# BMW_final.net
KiCad netlist of a schematic drawn in EAGLE
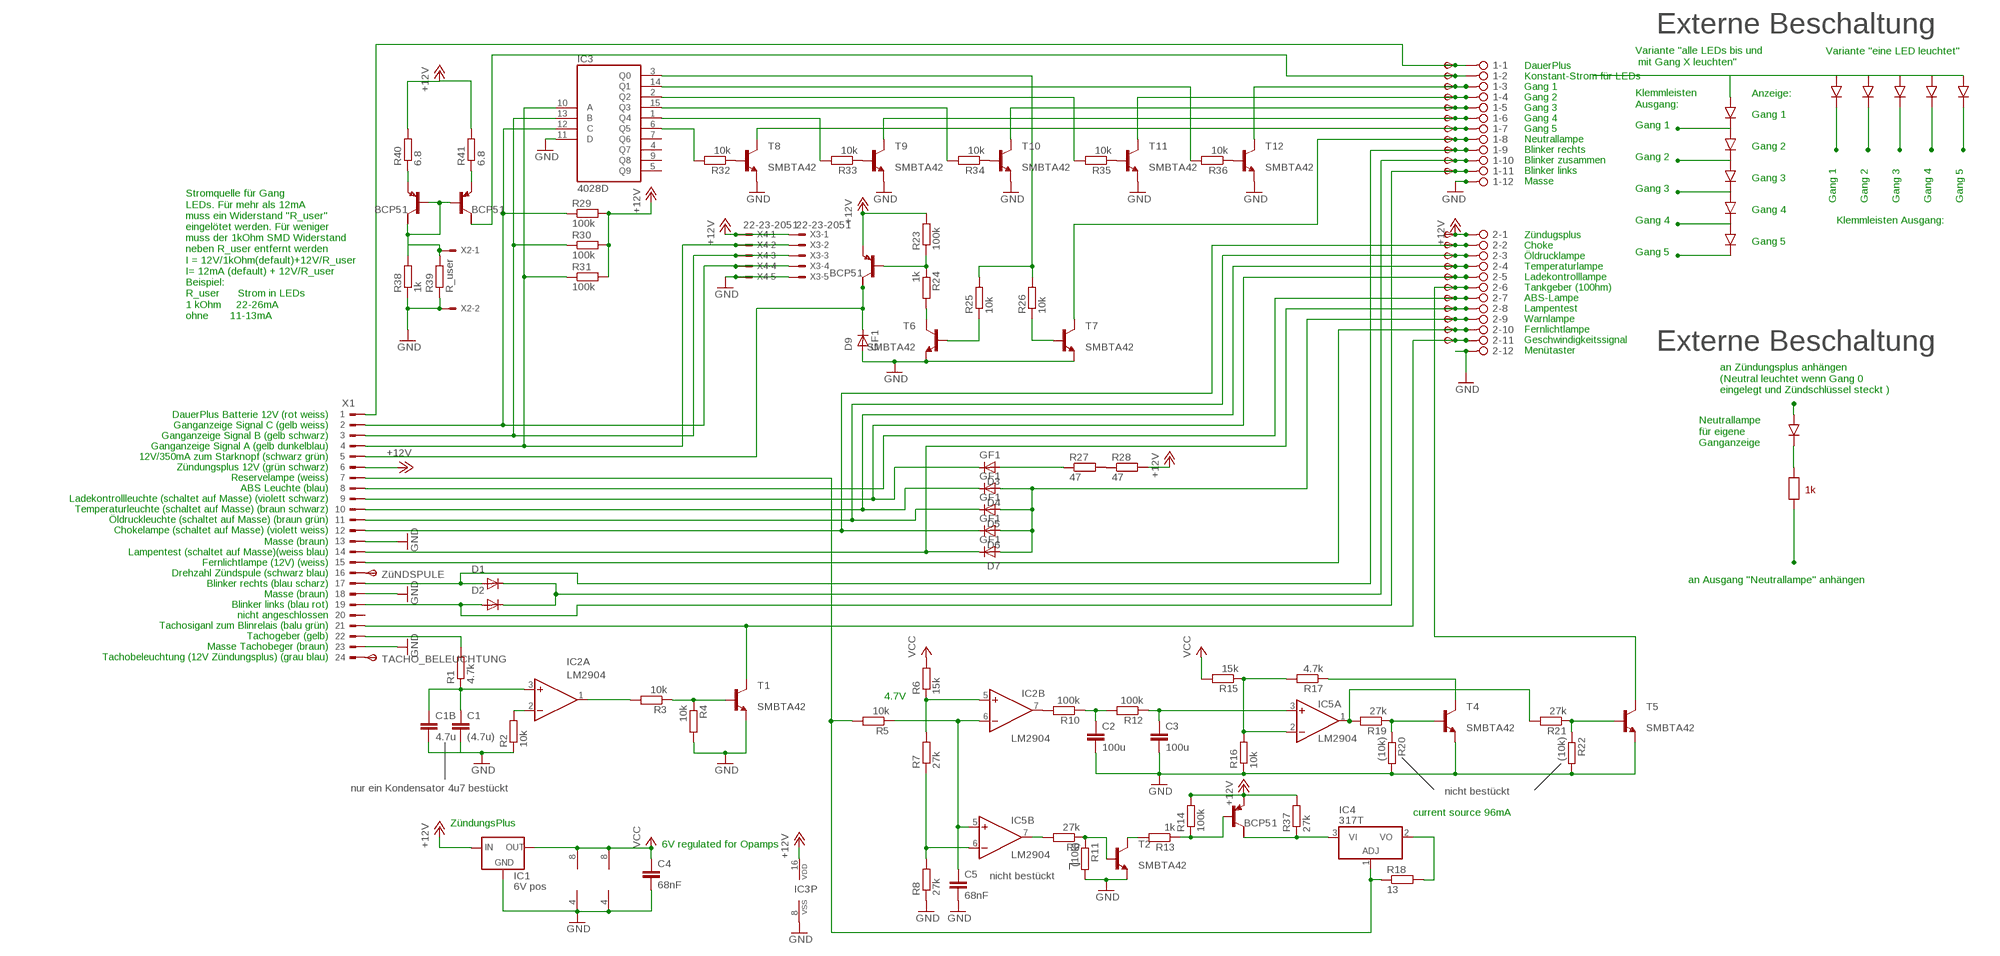
[diagram p0: schematic, sheet 1]

(export (version "E")
  (design (tool "Eeschema 10.0.6"))
  (components
    (comp (ref "1")
      (value "2081-1132")
      (footprint "eagle-import:12-PIN")
      (libsource (lib "eagle-import") (part "2081-1132"))
    )
    (comp (ref "2")
      (value "2081-1132")
      (footprint "eagle-import:12-PIN")
      (libsource (lib "eagle-import") (part "2081-1132"))
    )
    (comp (ref "C1")
      (value "(4.7u)")
      (footprint "eagle-import:C1206")
      (libsource (lib "eagle-import") (part "C-EUC1206"))
    )
    (comp (ref "C1B")
      (value "4.7u")
      (footprint "eagle-import:C0805K")
      (libsource (lib "eagle-import") (part "C-EUC0805K"))
    )
    (comp (ref "C2")
      (value "100u")
      (footprint "eagle-import:C1206K")
      (libsource (lib "eagle-import") (part "C-EUC1206K"))
    )
    (comp (ref "C3")
      (value "100u")
      (footprint "eagle-import:C1206K")
      (libsource (lib "eagle-import") (part "C-EUC1206K"))
    )
    (comp (ref "C4")
      (value "68nF")
      (footprint "eagle-import:C1206K")
      (libsource (lib "eagle-import") (part "C-EUC1206K"))
    )
    (comp (ref "C5")
      (value "68nF")
      (footprint "eagle-import:C1206K")
      (libsource (lib "eagle-import") (part "C-EUC1206K"))
    )
    (comp (ref "D1")
      (value "GF1")
      (footprint "eagle-import:SMA-DO214AC")
      (libsource (lib "eagle-import") (part "GF1"))
    )
    (comp (ref "D2")
      (value "GF1")
      (footprint "eagle-import:SMA-DO214AC")
      (libsource (lib "eagle-import") (part "GF1"))
    )
    (comp (ref "D3")
      (value "GF1")
      (footprint "eagle-import:SMA-DO214AC")
      (libsource (lib "eagle-import") (part "GF1"))
    )
    (comp (ref "D4")
      (value "GF1")
      (footprint "eagle-import:SMA-DO214AC")
      (libsource (lib "eagle-import") (part "GF1"))
    )
    (comp (ref "D5")
      (value "GF1")
      (footprint "eagle-import:SMA-DO214AC")
      (libsource (lib "eagle-import") (part "GF1"))
    )
    (comp (ref "D6")
      (value "GF1")
      (footprint "eagle-import:SMA-DO214AC")
      (libsource (lib "eagle-import") (part "GF1"))
    )
    (comp (ref "D7")
      (value "GF1")
      (footprint "eagle-import:SMA-DO214AC")
      (libsource (lib "eagle-import") (part "GF1"))
    )
    (comp (ref "D9")
      (value "GF1")
      (footprint "eagle-import:SMA-DO214AC")
      (libsource (lib "eagle-import") (part "GF1"))
    )
    (comp (ref "IC1")
      (value "6V pos")
      (footprint "eagle-import:78LXX")
      (libsource (lib "eagle-import") (part "78LXX"))
    )
    (comp (ref "IC2")
      (value "LM2904")
      (footprint "eagle-import:SO08")
      (fields (field (name "IC") "LM2904"))
      (libsource (lib "eagle-import") (part "LM358D"))
    )
    (comp (ref "IC3")
      (value "4028D")
      (footprint "eagle-import:SO16")
      (libsource (lib "eagle-import") (part "4028D"))
    )
    (comp (ref "IC4")
      (value "317T")
      (footprint "eagle-import:TO220H")
      (libsource (lib "eagle-import") (part "317T"))
    )
    (comp (ref "IC5")
      (value "LM2904")
      (footprint "eagle-import:SO08")
      (libsource (lib "eagle-import") (part "linear_BMW_LM358D"))
    )
    (comp (ref "R1")
      (value "4.7k")
      (footprint "eagle-import:R0805")
      (libsource (lib "eagle-import") (part "R-EU_R0805"))
    )
    (comp (ref "R2")
      (value "10k")
      (footprint "eagle-import:R0805")
      (libsource (lib "eagle-import") (part "R-EU_R0805"))
    )
    (comp (ref "R3")
      (value "10k")
      (footprint "eagle-import:R0805")
      (libsource (lib "eagle-import") (part "R-EU_R0805"))
    )
    (comp (ref "R4")
      (value "10k")
      (footprint "eagle-import:R0805")
      (libsource (lib "eagle-import") (part "R-EU_R0805"))
    )
    (comp (ref "R5")
      (value "10k")
      (footprint "eagle-import:R0805")
      (libsource (lib "eagle-import") (part "R-EU_R0805"))
    )
    (comp (ref "R6")
      (value "15k")
      (footprint "eagle-import:R0805")
      (libsource (lib "eagle-import") (part "R-EU_R0805"))
    )
    (comp (ref "R7")
      (value "27k")
      (footprint "eagle-import:R0805")
      (libsource (lib "eagle-import") (part "R-EU_R0805"))
    )
    (comp (ref "R8")
      (value "27k")
      (footprint "eagle-import:R0805")
      (libsource (lib "eagle-import") (part "R-EU_R0805"))
    )
    (comp (ref "R9")
      (value "27k")
      (footprint "eagle-import:R0805")
      (libsource (lib "eagle-import") (part "R-EU_R0805"))
    )
    (comp (ref "R10")
      (value "100k")
      (footprint "eagle-import:R0805")
      (libsource (lib "eagle-import") (part "R-EU_R0805"))
    )
    (comp (ref "R11")
      (value "(10k)")
      (footprint "eagle-import:R0805")
      (libsource (lib "eagle-import") (part "R-EU_R0805"))
    )
    (comp (ref "R12")
      (value "100k")
      (footprint "eagle-import:R0805")
      (libsource (lib "eagle-import") (part "R-EU_R0805"))
    )
    (comp (ref "R13")
      (value "1k")
      (footprint "eagle-import:R0805")
      (libsource (lib "eagle-import") (part "R-EU_R0805"))
    )
    (comp (ref "R14")
      (value "100k")
      (footprint "eagle-import:R0805")
      (libsource (lib "eagle-import") (part "R-EU_R0805"))
    )
    (comp (ref "R15")
      (value "15k")
      (footprint "eagle-import:R0805")
      (libsource (lib "eagle-import") (part "R-EU_R0805"))
    )
    (comp (ref "R16")
      (value "10k")
      (footprint "eagle-import:R0805")
      (libsource (lib "eagle-import") (part "R-EU_R0805"))
    )
    (comp (ref "R17")
      (value "4.7k")
      (footprint "eagle-import:R0805")
      (libsource (lib "eagle-import") (part "R-EU_R0805"))
    )
    (comp (ref "R18")
      (value "13")
      (footprint "eagle-import:0207_10")
      (libsource (lib "eagle-import") (part "R-EU_0207/10"))
    )
    (comp (ref "R19")
      (value "27k")
      (footprint "eagle-import:R0805")
      (libsource (lib "eagle-import") (part "R-EU_R0805"))
    )
    (comp (ref "R20")
      (value "(10k)")
      (footprint "eagle-import:R0805")
      (libsource (lib "eagle-import") (part "R-EU_R0805"))
    )
    (comp (ref "R21")
      (value "27k")
      (footprint "eagle-import:R0805")
      (libsource (lib "eagle-import") (part "R-EU_R0805"))
    )
    (comp (ref "R22")
      (value "(10k)")
      (footprint "eagle-import:R0805")
      (libsource (lib "eagle-import") (part "R-EU_R0805"))
    )
    (comp (ref "R23")
      (value "100k")
      (footprint "eagle-import:R0805")
      (libsource (lib "eagle-import") (part "R-EU_R0805"))
    )
    (comp (ref "R24")
      (value "1k")
      (footprint "eagle-import:R0805")
      (libsource (lib "eagle-import") (part "R-EU_R0805"))
    )
    (comp (ref "R25")
      (value "10k")
      (footprint "eagle-import:R0805")
      (libsource (lib "eagle-import") (part "R-EU_R0805"))
    )
    (comp (ref "R26")
      (value "10k")
      (footprint "eagle-import:R0805")
      (libsource (lib "eagle-import") (part "R-EU_R0805"))
    )
    (comp (ref "R27")
      (value "47")
      (footprint "eagle-import:V235_17")
      (libsource (lib "eagle-import") (part "R-EU_V235/17"))
    )
    (comp (ref "R28")
      (value "47")
      (footprint "eagle-import:V235_17")
      (libsource (lib "eagle-import") (part "R-EU_V235/17"))
    )
    (comp (ref "R29")
      (value "100k")
      (footprint "eagle-import:R0805")
      (libsource (lib "eagle-import") (part "R-EU_R0805"))
    )
    (comp (ref "R30")
      (value "100k")
      (footprint "eagle-import:R0805")
      (libsource (lib "eagle-import") (part "R-EU_R0805"))
    )
    (comp (ref "R31")
      (value "100k")
      (footprint "eagle-import:R0805")
      (libsource (lib "eagle-import") (part "R-EU_R0805"))
    )
    (comp (ref "R32")
      (value "10k")
      (footprint "eagle-import:R0805")
      (libsource (lib "eagle-import") (part "R-EU_R0805"))
    )
    (comp (ref "R33")
      (value "10k")
      (footprint "eagle-import:R0805")
      (libsource (lib "eagle-import") (part "R-EU_R0805"))
    )
    (comp (ref "R34")
      (value "10k")
      (footprint "eagle-import:R0805")
      (libsource (lib "eagle-import") (part "R-EU_R0805"))
    )
    (comp (ref "R35")
      (value "10k")
      (footprint "eagle-import:R0805")
      (libsource (lib "eagle-import") (part "R-EU_R0805"))
    )
    (comp (ref "R36")
      (value "10k")
      (footprint "eagle-import:R0805")
      (libsource (lib "eagle-import") (part "R-EU_R0805"))
    )
    (comp (ref "R37")
      (value "27k")
      (footprint "eagle-import:R0805")
      (libsource (lib "eagle-import") (part "R-EU_R0805"))
    )
    (comp (ref "R38")
      (value "1k")
      (footprint "eagle-import:R0805")
      (libsource (lib "eagle-import") (part "R-EU_R0805"))
    )
    (comp (ref "R39")
      (value "R_user")
      (footprint "eagle-import:R0805")
      (libsource (lib "eagle-import") (part "R-EU_R0805"))
    )
    (comp (ref "R40")
      (value "6.8")
      (footprint "eagle-import:R0805")
      (libsource (lib "eagle-import") (part "R-EU_R0805"))
    )
    (comp (ref "R41")
      (value "6.8")
      (footprint "eagle-import:R0805")
      (libsource (lib "eagle-import") (part "R-EU_R0805"))
    )
    (comp (ref "T")
      (value "BCP53T1")
      (footprint "eagle-import:SOT223")
      (fields (field (name "T") "BCP51"))
      (libsource (lib "eagle-import") (part "BCP53T1"))
    )
    (comp (ref "T1")
      (value "MMBTA42LT1-NPN-SOT23-BEC")
      (footprint "eagle-import:SOT23-BEC")
      (fields (field (name "T") "SMBTA42"))
      (libsource (lib "eagle-import") (part "-NPN-SOT23-BECMMBTA42LT1"))
    )
    (comp (ref "T2")
      (value "MMBTA42LT1-NPN-SOT23-BEC")
      (footprint "eagle-import:SOT23-BEC")
      (fields (field (name "T") "SMBTA42"))
      (libsource (lib "eagle-import") (part "-NPN-SOT23-BECMMBTA42LT1"))
    )
    (comp (ref "T3")
      (value "BCP53T1")
      (footprint "eagle-import:SOT223")
      (fields (field (name "T") "BCP51"))
      (libsource (lib "eagle-import") (part "BCP53T1"))
    )
    (comp (ref "T4")
      (value "MMBTA42LT1-NPN-SOT23-BEC")
      (footprint "eagle-import:SOT23-BEC")
      (fields (field (name "T") "SMBTA42"))
      (libsource (lib "eagle-import") (part "-NPN-SOT23-BECMMBTA42LT1"))
    )
    (comp (ref "T5")
      (value "MMBTA42LT1-NPN-SOT23-BEC")
      (footprint "eagle-import:SOT23-BEC")
      (fields (field (name "T") "SMBTA42"))
      (libsource (lib "eagle-import") (part "-NPN-SOT23-BECMMBTA42LT1"))
    )
    (comp (ref "T6")
      (value "MMBTA42LT1-NPN-SOT23-BEC")
      (footprint "eagle-import:SOT23-BEC")
      (fields (field (name "T") "SMBTA42"))
      (libsource (lib "eagle-import") (part "-NPN-SOT23-BECMMBTA42LT1"))
    )
    (comp (ref "T7")
      (value "MMBTA42LT1-NPN-SOT23-BEC")
      (footprint "eagle-import:SOT23-BEC")
      (fields (field (name "T") "SMBTA42"))
      (libsource (lib "eagle-import") (part "-NPN-SOT23-BECMMBTA42LT1"))
    )
    (comp (ref "T8")
      (value "MMBTA42LT1-NPN-SOT23-BEC")
      (footprint "eagle-import:SOT23-BEC")
      (fields (field (name "T") "SMBTA42"))
      (libsource (lib "eagle-import") (part "-NPN-SOT23-BECMMBTA42LT1"))
    )
    (comp (ref "T9")
      (value "MMBTA42LT1-NPN-SOT23-BEC")
      (footprint "eagle-import:SOT23-BEC")
      (fields (field (name "T") "SMBTA42"))
      (libsource (lib "eagle-import") (part "-NPN-SOT23-BECMMBTA42LT1"))
    )
    (comp (ref "T10")
      (value "MMBTA42LT1-NPN-SOT23-BEC")
      (footprint "eagle-import:SOT23-BEC")
      (fields (field (name "T") "SMBTA42"))
      (libsource (lib "eagle-import") (part "-NPN-SOT23-BECMMBTA42LT1"))
    )
    (comp (ref "T11")
      (value "MMBTA42LT1-NPN-SOT23-BEC")
      (footprint "eagle-import:SOT23-BEC")
      (fields (field (name "T") "SMBTA42"))
      (libsource (lib "eagle-import") (part "-NPN-SOT23-BECMMBTA42LT1"))
    )
    (comp (ref "T12")
      (value "MMBTA42LT1-NPN-SOT23-BEC")
      (footprint "eagle-import:SOT23-BEC")
      (fields (field (name "T") "SMBTA42"))
      (libsource (lib "eagle-import") (part "-NPN-SOT23-BECMMBTA42LT1"))
    )
    (comp (ref "T13")
      (value "BCP53T1")
      (footprint "eagle-import:SOT223")
      (fields (field (name "T") "BCP51"))
      (libsource (lib "eagle-import") (part "BCP53T1"))
    )
    (comp (ref "T14")
      (value "BCP53T1")
      (footprint "eagle-import:SOT223")
      (fields (field (name "T") "BCP51"))
      (libsource (lib "eagle-import") (part "BCP53T1"))
    )
    (comp (ref "TACHO_BELEUCHTUNG")
      (value "TPSP1_1MM")
      (footprint "eagle-import:P1_1.0MM")
      (libsource (lib "eagle-import") (part "TPSP1_1MM"))
    )
    (comp (ref "TP1")
      (value "TPSB1,27")
      (footprint "eagle-import:B1,27")
      (libsource (lib "eagle-import") (part "TPSB1,27"))
    )
    (comp (ref "TP2")
      (value "TPSB1,27")
      (footprint "eagle-import:B1,27")
      (libsource (lib "eagle-import") (part "TPSB1,27"))
    )
    (comp (ref "TP3")
      (value "TPSB1,27")
      (footprint "eagle-import:B1,27")
      (libsource (lib "eagle-import") (part "TPSB1,27"))
    )
    (comp (ref "TP4")
      (value "TPSB1,27")
      (footprint "eagle-import:B1,27")
      (libsource (lib "eagle-import") (part "TPSB1,27"))
    )
    (comp (ref "TP5")
      (value "TPSB1,27")
      (footprint "eagle-import:B1,27")
      (libsource (lib "eagle-import") (part "TPSB1,27"))
    )
    (comp (ref "TP6")
      (value "TPSB1,27")
      (footprint "eagle-import:B1,27")
      (libsource (lib "eagle-import") (part "TPSB1,27"))
    )
    (comp (ref "TP7")
      (value "TPSB1,27")
      (footprint "eagle-import:B1,27")
      (libsource (lib "eagle-import") (part "TPSB1,27"))
    )
    (comp (ref "TP8")
      (value "TPSB1,27")
      (footprint "eagle-import:B1,27")
      (libsource (lib "eagle-import") (part "TPSB1,27"))
    )
    (comp (ref "TP9")
      (value "TPSB1,27")
      (footprint "eagle-import:B1,27")
      (libsource (lib "eagle-import") (part "TPSB1,27"))
    )
    (comp (ref "TP10")
      (value "TPSB1,27")
      (footprint "eagle-import:B1,27")
      (libsource (lib "eagle-import") (part "TPSB1,27"))
    )
    (comp (ref "TP11")
      (value "TPSB1,27")
      (footprint "eagle-import:B1,27")
      (libsource (lib "eagle-import") (part "TPSB1,27"))
    )
    (comp (ref "TP12")
      (value "TPSB1,27")
      (footprint "eagle-import:B1,27")
      (libsource (lib "eagle-import") (part "TPSB1,27"))
    )
    (comp (ref "TP16")
      (value "TPSB1,27")
      (footprint "eagle-import:B1,27")
      (libsource (lib "eagle-import") (part "TPSB1,27"))
    )
    (comp (ref "TP17")
      (value "TPSB1,27")
      (footprint "eagle-import:B1,27")
      (libsource (lib "eagle-import") (part "TPSB1,27"))
    )
    (comp (ref "TP18")
      (value "TPSB1,27")
      (footprint "eagle-import:B1,27")
      (libsource (lib "eagle-import") (part "TPSB1,27"))
    )
    (comp (ref "TP19")
      (value "TPSB1,27")
      (footprint "eagle-import:B1,27")
      (libsource (lib "eagle-import") (part "TPSB1,27"))
    )
    (comp (ref "TP21")
      (value "TPSB1,27")
      (footprint "eagle-import:B1,27")
      (libsource (lib "eagle-import") (part "TPSB1,27"))
    )
    (comp (ref "TP22")
      (value "TPSB1,27")
      (footprint "eagle-import:B1,27")
      (libsource (lib "eagle-import") (part "TPSB1,27"))
    )
    (comp (ref "TP23")
      (value "TPSB1,27")
      (footprint "eagle-import:B1,27")
      (libsource (lib "eagle-import") (part "TPSB1,27"))
    )
    (comp (ref "TP24")
      (value "TPSB1,27")
      (footprint "eagle-import:B1,27")
      (libsource (lib "eagle-import") (part "TPSB1,27"))
    )
    (comp (ref "TP25")
      (value "TPSB1,27")
      (footprint "eagle-import:B1,27")
      (libsource (lib "eagle-import") (part "TPSB1,27"))
    )
    (comp (ref "TP26")
      (value "TPSB1,27")
      (footprint "eagle-import:B1,27")
      (libsource (lib "eagle-import") (part "TPSB1,27"))
    )
    (comp (ref "X1")
      (value "CON_BMW")
      (footprint "eagle-import:24-PIN")
      (libsource (lib "eagle-import") (part "CON_BMW"))
    )
    (comp (ref "X2")
      (value "22-23-2021")
      (footprint "eagle-import:22-23-2021")
      (fields (field (name "MF") "MOLEX"))
      (libsource (lib "eagle-import") (part "22-23-2021"))
    )
    (comp (ref "X3")
      (value "22-23-2051")
      (footprint "eagle-import:22-23-2051")
      (fields (field (name "MF") "MOLEX"))
      (libsource (lib "eagle-import") (part "22-23-2051"))
    )
    (comp (ref "X4")
      (value "22-23-2051")
      (footprint "eagle-import:22-23-2051")
      (fields (field (name "MF") "MOLEX"))
      (libsource (lib "eagle-import") (part "22-23-2051"))
    )
    (comp (ref "ZüNDSPULE")
      (value "TPSP1_1MM")
      (footprint "eagle-import:P1_1.0MM")
      (libsource (lib "eagle-import") (part "TPSP1_1MM"))
    )
  )
  (nets
    (net (code "1") (name "+12V") (class "Default")
      (node (ref "2") (pin "1") (pinfunction "KL_1") (pintype "passive"))
      (node (ref "IC1") (pin "IN") (pinfunction "IN_IN") (pintype "input"))
      (node (ref "IC3") (pin "16") (pinfunction "VDD_16") (pintype "power_in"))
      (node (ref "R14") (pin "2") (pinfunction "2_2") (pintype "passive"))
      (node (ref "R23") (pin "2") (pinfunction "2_2") (pintype "passive"))
      (node (ref "R28") (pin "2") (pinfunction "2_2") (pintype "passive"))
      (node (ref "R29") (pin "2") (pinfunction "2_2") (pintype "passive"))
      (node (ref "R30") (pin "2") (pinfunction "2_2") (pintype "passive"))
      (node (ref "R31") (pin "2") (pinfunction "2_2") (pintype "passive"))
      (node (ref "R37") (pin "2") (pinfunction "2_2") (pintype "passive"))
      (node (ref "R40") (pin "2") (pinfunction "2_2") (pintype "passive"))
      (node (ref "R41") (pin "2") (pinfunction "2_2") (pintype "passive"))
      (node (ref "T") (pin "3") (pinfunction "E_3") (pintype "passive"))
      (node (ref "T3") (pin "3") (pinfunction "E_3") (pintype "passive"))
      (node (ref "TP12") (pin "TP") (pinfunction "PP_TP") (pintype "input"))
      (node (ref "X1") (pin "6") (pinfunction "6_6") (pintype "passive"))
      (node (ref "X3") (pin "1") (pinfunction "S_1") (pintype "passive"))
      (node (ref "X4") (pin "1") (pinfunction "S_1") (pintype "passive"))
    )
    (net (code "2") (name "GND") (class "Default")
      (node (ref "1") (pin "12") (pinfunction "KL_12") (pintype "passive"))
      (node (ref "2") (pin "12") (pinfunction "KL_12") (pintype "passive"))
      (node (ref "C1") (pin "2") (pinfunction "2_2") (pintype "passive"))
      (node (ref "C1B") (pin "2") (pinfunction "2_2") (pintype "passive"))
      (node (ref "C2") (pin "2") (pinfunction "2_2") (pintype "passive"))
      (node (ref "C3") (pin "2") (pinfunction "2_2") (pintype "passive"))
      (node (ref "C4") (pin "2") (pinfunction "2_2") (pintype "passive"))
      (node (ref "C5") (pin "2") (pinfunction "2_2") (pintype "passive"))
      (node (ref "D9") (pin "A") (pinfunction "A_A") (pintype "passive"))
      (node (ref "IC1") (pin "GND") (pinfunction "GND_GND") (pintype "input"))
      (node (ref "IC2") (pin "4") (pinfunction "V-_4") (pintype "power_in"))
      (node (ref "IC3") (pin "11") (pinfunction "D_11") (pintype "input"))
      (node (ref "IC3") (pin "8") (pinfunction "VSS_8") (pintype "power_in"))
      (node (ref "IC5") (pin "4") (pinfunction "V-_4") (pintype "power_in"))
      (node (ref "R11") (pin "2") (pinfunction "2_2") (pintype "passive"))
      (node (ref "R16") (pin "1") (pinfunction "1_1") (pintype "passive"))
      (node (ref "R2") (pin "1") (pinfunction "1_1") (pintype "passive"))
      (node (ref "R20") (pin "2") (pinfunction "2_2") (pintype "passive"))
      (node (ref "R22") (pin "2") (pinfunction "2_2") (pintype "passive"))
      (node (ref "R38") (pin "1") (pinfunction "1_1") (pintype "passive"))
      (node (ref "R39") (pin "1") (pinfunction "1_1") (pintype "passive"))
      (node (ref "R4") (pin "2") (pinfunction "2_2") (pintype "passive"))
      (node (ref "R8") (pin "1") (pinfunction "1_1") (pintype "passive"))
      (node (ref "T1") (pin "E") (pinfunction "E_E") (pintype "passive"))
      (node (ref "T10") (pin "E") (pinfunction "E_E") (pintype "passive"))
      (node (ref "T11") (pin "E") (pinfunction "E_E") (pintype "passive"))
      (node (ref "T12") (pin "E") (pinfunction "E_E") (pintype "passive"))
      (node (ref "T2") (pin "E") (pinfunction "E_E") (pintype "passive"))
      (node (ref "T4") (pin "E") (pinfunction "E_E") (pintype "passive"))
      (node (ref "T5") (pin "E") (pinfunction "E_E") (pintype "passive"))
      (node (ref "T6") (pin "E") (pinfunction "E_E") (pintype "passive"))
      (node (ref "T7") (pin "E") (pinfunction "E_E") (pintype "passive"))
      (node (ref "T8") (pin "E") (pinfunction "E_E") (pintype "passive"))
      (node (ref "T9") (pin "E") (pinfunction "E_E") (pintype "passive"))
      (node (ref "X1") (pin "13") (pinfunction "13_13") (pintype "passive"))
      (node (ref "X1") (pin "18") (pinfunction "18_18") (pintype "passive"))
      (node (ref "X1") (pin "23") (pinfunction "23_23") (pintype "passive"))
      (node (ref "X2") (pin "2") (pinfunction "S_2") (pintype "passive"))
      (node (ref "X3") (pin "5") (pinfunction "S_5") (pintype "passive"))
      (node (ref "X4") (pin "5") (pinfunction "S_5") (pintype "passive"))
    )
    (net (code "3") (name "Net-(1A-KL)") (class "Default")
      (node (ref "1") (pin "1") (pinfunction "KL_1") (pintype "passive"))
      (node (ref "TP1") (pin "TP") (pinfunction "PP_TP") (pintype "input"))
      (node (ref "X1") (pin "1") (pinfunction "1_1") (pintype "passive"))
    )
    (net (code "4") (name "Net-(1B-KL)") (class "Default")
      (node (ref "1") (pin "10") (pinfunction "KL_10") (pintype "passive"))
      (node (ref "D1") (pin "K") (pinfunction "C_K") (pintype "passive"))
      (node (ref "D2") (pin "K") (pinfunction "C_K") (pintype "passive"))
      (node (ref "TP10") (pin "TP") (pinfunction "PP_TP") (pintype "input"))
    )
    (net (code "5") (name "Net-(1C-KL)") (class "Default")
      (node (ref "1") (pin "11") (pinfunction "KL_11") (pintype "passive"))
      (node (ref "D2") (pin "A") (pinfunction "A_A") (pintype "passive"))
      (node (ref "TP11") (pin "TP") (pinfunction "PP_TP") (pintype "input"))
      (node (ref "X1") (pin "19") (pinfunction "19_19") (pintype "passive"))
    )
    (net (code "6") (name "Net-(1E-KL)") (class "Default")
      (node (ref "1") (pin "2") (pinfunction "KL_2") (pintype "passive"))
      (node (ref "T14") (pin "2") (pinfunction "C_2") (pintype "passive"))
      (node (ref "TP2") (pin "TP") (pinfunction "PP_TP") (pintype "input"))
    )
    (net (code "7") (name "Net-(1F-KL)") (class "Default")
      (node (ref "1") (pin "3") (pinfunction "KL_3") (pintype "passive"))
      (node (ref "T12") (pin "C") (pinfunction "C_C") (pintype "passive"))
      (node (ref "TP3") (pin "TP") (pinfunction "PP_TP") (pintype "input"))
    )
    (net (code "8") (name "Net-(1G-KL)") (class "Default")
      (node (ref "1") (pin "4") (pinfunction "KL_4") (pintype "passive"))
      (node (ref "T11") (pin "C") (pinfunction "C_C") (pintype "passive"))
      (node (ref "TP4") (pin "TP") (pinfunction "PP_TP") (pintype "input"))
    )
    (net (code "9") (name "Net-(1H-KL)") (class "Default")
      (node (ref "1") (pin "5") (pinfunction "KL_5") (pintype "passive"))
      (node (ref "T10") (pin "C") (pinfunction "C_C") (pintype "passive"))
      (node (ref "TP5") (pin "TP") (pinfunction "PP_TP") (pintype "input"))
    )
    (net (code "10") (name "Net-(1I-KL)") (class "Default")
      (node (ref "1") (pin "6") (pinfunction "KL_6") (pintype "passive"))
      (node (ref "T9") (pin "C") (pinfunction "C_C") (pintype "passive"))
      (node (ref "TP6") (pin "TP") (pinfunction "PP_TP") (pintype "input"))
    )
    (net (code "11") (name "Net-(1J-KL)") (class "Default")
      (node (ref "1") (pin "7") (pinfunction "KL_7") (pintype "passive"))
      (node (ref "T8") (pin "C") (pinfunction "C_C") (pintype "passive"))
      (node (ref "TP7") (pin "TP") (pinfunction "PP_TP") (pintype "input"))
    )
    (net (code "12") (name "Net-(1K-KL)") (class "Default")
      (node (ref "1") (pin "8") (pinfunction "KL_8") (pintype "passive"))
      (node (ref "T7") (pin "C") (pinfunction "C_C") (pintype "passive"))
      (node (ref "TP8") (pin "TP") (pinfunction "PP_TP") (pintype "input"))
    )
    (net (code "13") (name "Net-(1L-KL)") (class "Default")
      (node (ref "1") (pin "9") (pinfunction "KL_9") (pintype "passive"))
      (node (ref "D1") (pin "A") (pinfunction "A_A") (pintype "passive"))
      (node (ref "TP9") (pin "TP") (pinfunction "PP_TP") (pintype "input"))
      (node (ref "X1") (pin "17") (pinfunction "17_17") (pintype "passive"))
    )
    (net (code "14") (name "Net-(2B-KL)") (class "Default")
      (node (ref "2") (pin "10") (pinfunction "KL_10") (pintype "passive"))
      (node (ref "TP25") (pin "TP") (pinfunction "PP_TP") (pintype "input"))
      (node (ref "X1") (pin "15") (pinfunction "15_15") (pintype "passive"))
    )
    (net (code "15") (name "Net-(2C-KL)") (class "Default")
      (node (ref "2") (pin "11") (pinfunction "KL_11") (pintype "passive"))
      (node (ref "T1") (pin "C") (pinfunction "C_C") (pintype "passive"))
      (node (ref "TP26") (pin "TP") (pinfunction "PP_TP") (pintype "input"))
      (node (ref "X1") (pin "21") (pinfunction "21_21") (pintype "passive"))
    )
    (net (code "16") (name "Net-(2E-KL)") (class "Default")
      (node (ref "2") (pin "2") (pinfunction "KL_2") (pintype "passive"))
      (node (ref "D6") (pin "K") (pinfunction "C_K") (pintype "passive"))
      (node (ref "TP16") (pin "TP") (pinfunction "PP_TP") (pintype "input"))
      (node (ref "X1") (pin "12") (pinfunction "12_12") (pintype "passive"))
    )
    (net (code "17") (name "Net-(2F-KL)") (class "Default")
      (node (ref "2") (pin "3") (pinfunction "KL_3") (pintype "passive"))
      (node (ref "D5") (pin "K") (pinfunction "C_K") (pintype "passive"))
      (node (ref "TP17") (pin "TP") (pinfunction "PP_TP") (pintype "input"))
      (node (ref "X1") (pin "11") (pinfunction "11_11") (pintype "passive"))
    )
    (net (code "18") (name "Net-(2G-KL)") (class "Default")
      (node (ref "2") (pin "4") (pinfunction "KL_4") (pintype "passive"))
      (node (ref "D4") (pin "K") (pinfunction "C_K") (pintype "passive"))
      (node (ref "TP18") (pin "TP") (pinfunction "PP_TP") (pintype "input"))
      (node (ref "X1") (pin "10") (pinfunction "10_10") (pintype "passive"))
    )
    (net (code "19") (name "Net-(2H-KL)") (class "Default")
      (node (ref "2") (pin "5") (pinfunction "KL_5") (pintype "passive"))
      (node (ref "D3") (pin "K") (pinfunction "C_K") (pintype "passive"))
      (node (ref "TP19") (pin "TP") (pinfunction "PP_TP") (pintype "input"))
      (node (ref "X1") (pin "9") (pinfunction "9_9") (pintype "passive"))
    )
    (net (code "20") (name "Net-(2I-KL)") (class "Default")
      (node (ref "2") (pin "6") (pinfunction "KL_6") (pintype "passive"))
      (node (ref "T5") (pin "C") (pinfunction "C_C") (pintype "passive"))
      (node (ref "TP21") (pin "TP") (pinfunction "PP_TP") (pintype "input"))
    )
    (net (code "21") (name "Net-(2J-KL)") (class "Default")
      (node (ref "2") (pin "7") (pinfunction "KL_7") (pintype "passive"))
      (node (ref "TP22") (pin "TP") (pinfunction "PP_TP") (pintype "input"))
      (node (ref "X1") (pin "8") (pinfunction "8_8") (pintype "passive"))
    )
    (net (code "22") (name "Net-(2K-KL)") (class "Default")
      (node (ref "2") (pin "8") (pinfunction "KL_8") (pintype "passive"))
      (node (ref "D7") (pin "K") (pinfunction "C_K") (pintype "passive"))
      (node (ref "TP23") (pin "TP") (pinfunction "PP_TP") (pintype "input"))
      (node (ref "X1") (pin "14") (pinfunction "14_14") (pintype "passive"))
    )
    (net (code "23") (name "Net-(2L-KL)") (class "Default")
      (node (ref "2") (pin "9") (pinfunction "KL_9") (pintype "passive"))
      (node (ref "D4") (pin "A") (pinfunction "A_A") (pintype "passive"))
      (node (ref "D5") (pin "A") (pinfunction "A_A") (pintype "passive"))
      (node (ref "D6") (pin "A") (pinfunction "A_A") (pintype "passive"))
      (node (ref "D7") (pin "A") (pinfunction "A_A") (pintype "passive"))
      (node (ref "TP24") (pin "TP") (pinfunction "PP_TP") (pintype "input"))
    )
    (net (code "24") (name "Net-(C2-Pad1)") (class "Default")
      (node (ref "C2") (pin "1") (pinfunction "1_1") (pintype "passive"))
      (node (ref "R10") (pin "1") (pinfunction "1_1") (pintype "passive"))
      (node (ref "R12") (pin "2") (pinfunction "2_2") (pintype "passive"))
    )
    (net (code "25") (name "Net-(D3-PadA)") (class "Default")
      (node (ref "D3") (pin "A") (pinfunction "A_A") (pintype "passive"))
      (node (ref "R27") (pin "1") (pinfunction "1_1") (pintype "passive"))
    )
    (net (code "26") (name "Net-(D9-C)") (class "Default")
      (node (ref "D9") (pin "K") (pinfunction "C_K") (pintype "passive"))
      (node (ref "T") (pin "2") (pinfunction "C_2") (pintype "passive"))
      (node (ref "X1") (pin "5") (pinfunction "5_5") (pintype "passive"))
    )
    (net (code "27") (name "Net-(IC2A-+IN)") (class "Default")
      (node (ref "C1") (pin "1") (pinfunction "1_1") (pintype "passive"))
      (node (ref "C1B") (pin "1") (pinfunction "1_1") (pintype "passive"))
      (node (ref "IC2") (pin "3") (pinfunction "+IN_3") (pintype "input"))
      (node (ref "R1") (pin "1") (pinfunction "1_1") (pintype "passive"))
    )
    (net (code "28") (name "Net-(IC2A--IN)") (class "Default")
      (node (ref "IC2") (pin "2") (pinfunction "-IN_2") (pintype "input"))
      (node (ref "R2") (pin "2") (pinfunction "2_2") (pintype "passive"))
    )
    (net (code "29") (name "Net-(IC2A-OUT)") (class "Default")
      (node (ref "IC2") (pin "1") (pinfunction "OUT_1") (pintype "output"))
      (node (ref "R3") (pin "2") (pinfunction "2_2") (pintype "passive"))
    )
    (net (code "30") (name "Net-(IC2B-+IN)") (class "Default")
      (node (ref "IC2") (pin "5") (pinfunction "+IN_5") (pintype "input"))
      (node (ref "R6") (pin "1") (pinfunction "1_1") (pintype "passive"))
      (node (ref "R7") (pin "2") (pinfunction "2_2") (pintype "passive"))
    )
    (net (code "31") (name "Net-(IC2B--IN)") (class "Default")
      (node (ref "C5") (pin "1") (pinfunction "1_1") (pintype "passive"))
      (node (ref "IC2") (pin "6") (pinfunction "-IN_6") (pintype "input"))
      (node (ref "IC5") (pin "5") (pinfunction "+IN_5") (pintype "input"))
      (node (ref "R5") (pin "1") (pinfunction "1_1") (pintype "passive"))
    )
    (net (code "32") (name "Net-(IC2B-OUT)") (class "Default")
      (node (ref "IC2") (pin "7") (pinfunction "OUT_7") (pintype "output"))
      (node (ref "R10") (pin "2") (pinfunction "2_2") (pintype "passive"))
    )
    (net (code "33") (name "Net-(IC3A-A)") (class "Default")
      (node (ref "IC3") (pin "10") (pinfunction "A_10") (pintype "input"))
      (node (ref "R31") (pin "1") (pinfunction "1_1") (pintype "passive"))
      (node (ref "X1") (pin "4") (pinfunction "4_4") (pintype "passive"))
      (node (ref "X3") (pin "2") (pinfunction "S_2") (pintype "passive"))
      (node (ref "X4") (pin "2") (pinfunction "S_2") (pintype "passive"))
    )
    (net (code "34") (name "Net-(IC3A-B)") (class "Default")
      (node (ref "IC3") (pin "13") (pinfunction "B_13") (pintype "input"))
      (node (ref "R30") (pin "1") (pinfunction "1_1") (pintype "passive"))
      (node (ref "X1") (pin "3") (pinfunction "3_3") (pintype "passive"))
      (node (ref "X3") (pin "3") (pinfunction "S_3") (pintype "passive"))
      (node (ref "X4") (pin "3") (pinfunction "S_3") (pintype "passive"))
    )
    (net (code "35") (name "Net-(IC3A-C)") (class "Default")
      (node (ref "IC3") (pin "12") (pinfunction "C_12") (pintype "input"))
      (node (ref "R29") (pin "1") (pinfunction "1_1") (pintype "passive"))
      (node (ref "X1") (pin "2") (pinfunction "2_2") (pintype "passive"))
      (node (ref "X3") (pin "4") (pinfunction "S_4") (pintype "passive"))
      (node (ref "X4") (pin "4") (pinfunction "S_4") (pintype "passive"))
    )
    (net (code "36") (name "Net-(IC3A-Q0)") (class "Default")
      (node (ref "IC3") (pin "3") (pinfunction "Q0_3") (pintype "output"))
      (node (ref "R25") (pin "2") (pinfunction "2_2") (pintype "passive"))
      (node (ref "R26") (pin "2") (pinfunction "2_2") (pintype "passive"))
    )
    (net (code "37") (name "Net-(IC3A-Q1)") (class "Default")
      (node (ref "IC3") (pin "14") (pinfunction "Q1_14") (pintype "output"))
      (node (ref "R36") (pin "2") (pinfunction "2_2") (pintype "passive"))
    )
    (net (code "38") (name "Net-(IC3A-Q2)") (class "Default")
      (node (ref "IC3") (pin "2") (pinfunction "Q2_2") (pintype "output"))
      (node (ref "R35") (pin "2") (pinfunction "2_2") (pintype "passive"))
    )
    (net (code "39") (name "Net-(IC3A-Q3)") (class "Default")
      (node (ref "IC3") (pin "15") (pinfunction "Q3_15") (pintype "output"))
      (node (ref "R34") (pin "2") (pinfunction "2_2") (pintype "passive"))
    )
    (net (code "40") (name "Net-(IC3A-Q4)") (class "Default")
      (node (ref "IC3") (pin "1") (pinfunction "Q4_1") (pintype "output"))
      (node (ref "R33") (pin "2") (pinfunction "2_2") (pintype "passive"))
    )
    (net (code "41") (name "Net-(IC3A-Q5)") (class "Default")
      (node (ref "IC3") (pin "6") (pinfunction "Q5_6") (pintype "output"))
      (node (ref "R32") (pin "2") (pinfunction "2_2") (pintype "passive"))
    )
    (net (code "42") (name "Net-(IC4-ADJ)") (class "Default")
      (node (ref "IC4") (pin "1") (pinfunction "ADJ_1") (pintype "input"))
      (node (ref "R18") (pin "1") (pinfunction "1_1") (pintype "passive"))
      (node (ref "R5") (pin "2") (pinfunction "2_2") (pintype "passive"))
      (node (ref "X1") (pin "7") (pinfunction "7_7") (pintype "passive"))
    )
    (net (code "43") (name "Net-(IC4-VI)") (class "Default")
      (node (ref "IC4") (pin "3") (pinfunction "VI_3") (pintype "input"))
      (node (ref "R37") (pin "1") (pinfunction "1_1") (pintype "passive"))
      (node (ref "T3") (pin "2") (pinfunction "C_2") (pintype "passive"))
    )
    (net (code "44") (name "Net-(IC4-VO)") (class "Default")
      (node (ref "IC4") (pin "2") (pinfunction "VO_2") (pintype "passive"))
      (node (ref "R18") (pin "2") (pinfunction "2_2") (pintype "passive"))
    )
    (net (code "45") (name "Net-(IC5A-+IN)") (class "Default")
      (node (ref "C3") (pin "1") (pinfunction "1_1") (pintype "passive"))
      (node (ref "IC5") (pin "3") (pinfunction "+IN_3") (pintype "input"))
      (node (ref "R12") (pin "1") (pinfunction "1_1") (pintype "passive"))
    )
    (net (code "46") (name "Net-(IC5A--IN)") (class "Default")
      (node (ref "IC5") (pin "2") (pinfunction "-IN_2") (pintype "input"))
      (node (ref "R15") (pin "1") (pinfunction "1_1") (pintype "passive"))
      (node (ref "R16") (pin "2") (pinfunction "2_2") (pintype "passive"))
      (node (ref "R17") (pin "2") (pinfunction "2_2") (pintype "passive"))
    )
    (net (code "47") (name "Net-(IC5A-OUT)") (class "Default")
      (node (ref "IC5") (pin "1") (pinfunction "OUT_1") (pintype "output"))
      (node (ref "R19") (pin "2") (pinfunction "2_2") (pintype "passive"))
      (node (ref "R21") (pin "2") (pinfunction "2_2") (pintype "passive"))
    )
    (net (code "48") (name "Net-(IC5B--IN)") (class "Default")
      (node (ref "IC5") (pin "6") (pinfunction "-IN_6") (pintype "input"))
      (node (ref "R7") (pin "1") (pinfunction "1_1") (pintype "passive"))
      (node (ref "R8") (pin "2") (pinfunction "2_2") (pintype "passive"))
    )
    (net (code "49") (name "Net-(IC5B-OUT)") (class "Default")
      (node (ref "IC5") (pin "7") (pinfunction "OUT_7") (pintype "output"))
      (node (ref "R9") (pin "2") (pinfunction "2_2") (pintype "passive"))
    )
    (net (code "50") (name "Net-(R1-Pad2)") (class "Default")
      (node (ref "R1") (pin "2") (pinfunction "2_2") (pintype "passive"))
      (node (ref "X1") (pin "22") (pinfunction "22_22") (pintype "passive"))
    )
    (net (code "51") (name "Net-(R3-Pad1)") (class "Default")
      (node (ref "R3") (pin "1") (pinfunction "1_1") (pintype "passive"))
      (node (ref "R4") (pin "1") (pinfunction "1_1") (pintype "passive"))
      (node (ref "T1") (pin "B") (pinfunction "B_B") (pintype "passive"))
    )
    (net (code "52") (name "Net-(R11-Pad1)") (class "Default")
      (node (ref "R11") (pin "1") (pinfunction "1_1") (pintype "passive"))
      (node (ref "R9") (pin "1") (pinfunction "1_1") (pintype "passive"))
      (node (ref "T2") (pin "B") (pinfunction "B_B") (pintype "passive"))
    )
    (net (code "53") (name "Net-(R13-Pad2)") (class "Default")
      (node (ref "R13") (pin "2") (pinfunction "2_2") (pintype "passive"))
      (node (ref "T2") (pin "C") (pinfunction "C_C") (pintype "passive"))
    )
    (net (code "54") (name "Net-(R17-Pad1)") (class "Default")
      (node (ref "R17") (pin "1") (pinfunction "1_1") (pintype "passive"))
      (node (ref "T4") (pin "C") (pinfunction "C_C") (pintype "passive"))
    )
    (net (code "55") (name "Net-(R19-Pad1)") (class "Default")
      (node (ref "R19") (pin "1") (pinfunction "1_1") (pintype "passive"))
      (node (ref "R20") (pin "1") (pinfunction "1_1") (pintype "passive"))
      (node (ref "T4") (pin "B") (pinfunction "B_B") (pintype "passive"))
    )
    (net (code "56") (name "Net-(R21-Pad1)") (class "Default")
      (node (ref "R21") (pin "1") (pinfunction "1_1") (pintype "passive"))
      (node (ref "R22") (pin "1") (pinfunction "1_1") (pintype "passive"))
      (node (ref "T5") (pin "B") (pinfunction "B_B") (pintype "passive"))
    )
    (net (code "57") (name "Net-(R24-Pad2)") (class "Default")
      (node (ref "R24") (pin "2") (pinfunction "2_2") (pintype "passive"))
      (node (ref "T6") (pin "C") (pinfunction "C_C") (pintype "passive"))
    )
    (net (code "58") (name "Net-(R25-Pad1)") (class "Default")
      (node (ref "R25") (pin "1") (pinfunction "1_1") (pintype "passive"))
      (node (ref "T6") (pin "B") (pinfunction "B_B") (pintype "passive"))
    )
    (net (code "59") (name "Net-(R26-Pad1)") (class "Default")
      (node (ref "R26") (pin "1") (pinfunction "1_1") (pintype "passive"))
      (node (ref "T7") (pin "B") (pinfunction "B_B") (pintype "passive"))
    )
    (net (code "60") (name "Net-(R27-Pad2)") (class "Default")
      (node (ref "R27") (pin "2") (pinfunction "2_2") (pintype "passive"))
      (node (ref "R28") (pin "1") (pinfunction "1_1") (pintype "passive"))
    )
    (net (code "61") (name "Net-(R32-Pad1)") (class "Default")
      (node (ref "R32") (pin "1") (pinfunction "1_1") (pintype "passive"))
      (node (ref "T8") (pin "B") (pinfunction "B_B") (pintype "passive"))
    )
    (net (code "62") (name "Net-(R33-Pad1)") (class "Default")
      (node (ref "R33") (pin "1") (pinfunction "1_1") (pintype "passive"))
      (node (ref "T9") (pin "B") (pinfunction "B_B") (pintype "passive"))
    )
    (net (code "63") (name "Net-(R34-Pad1)") (class "Default")
      (node (ref "R34") (pin "1") (pinfunction "1_1") (pintype "passive"))
      (node (ref "T10") (pin "B") (pinfunction "B_B") (pintype "passive"))
    )
    (net (code "64") (name "Net-(R35-Pad1)") (class "Default")
      (node (ref "R35") (pin "1") (pinfunction "1_1") (pintype "passive"))
      (node (ref "T11") (pin "B") (pinfunction "B_B") (pintype "passive"))
    )
    (net (code "65") (name "Net-(R36-Pad1)") (class "Default")
      (node (ref "R36") (pin "1") (pinfunction "1_1") (pintype "passive"))
      (node (ref "T12") (pin "B") (pinfunction "B_B") (pintype "passive"))
    )
    (net (code "66") (name "Net-(T-B)") (class "Default")
      (node (ref "R23") (pin "1") (pinfunction "1_1") (pintype "passive"))
      (node (ref "R24") (pin "1") (pinfunction "1_1") (pintype "passive"))
      (node (ref "T") (pin "1") (pinfunction "B_1") (pintype "passive"))
    )
    (net (code "67") (name "Net-(T3-B)") (class "Default")
      (node (ref "R13") (pin "1") (pinfunction "1_1") (pintype "passive"))
      (node (ref "R14") (pin "1") (pinfunction "1_1") (pintype "passive"))
      (node (ref "T3") (pin "1") (pinfunction "B_1") (pintype "passive"))
    )
    (net (code "68") (name "Net-(T13-B)") (class "Default")
      (node (ref "R38") (pin "2") (pinfunction "2_2") (pintype "passive"))
      (node (ref "R39") (pin "2") (pinfunction "2_2") (pintype "passive"))
      (node (ref "T13") (pin "1") (pinfunction "B_1") (pintype "passive"))
      (node (ref "T13") (pin "2") (pinfunction "C_2") (pintype "passive"))
      (node (ref "T14") (pin "1") (pinfunction "B_1") (pintype "passive"))
      (node (ref "X2") (pin "1") (pinfunction "S_1") (pintype "passive"))
    )
    (net (code "69") (name "Net-(T13-E)") (class "Default")
      (node (ref "R40") (pin "1") (pinfunction "1_1") (pintype "passive"))
      (node (ref "T13") (pin "3") (pinfunction "E_3") (pintype "passive"))
    )
    (net (code "70") (name "Net-(T14-E)") (class "Default")
      (node (ref "R41") (pin "1") (pinfunction "1_1") (pintype "passive"))
      (node (ref "T14") (pin "3") (pinfunction "E_3") (pintype "passive"))
    )
    (net (code "71") (name "Net-(TACHO_BELEUCHTUNG-PP)") (class "Default")
      (node (ref "TACHO_BELEUCHTUNG") (pin "TP") (pinfunction "PP_TP") (pintype "input"))
      (node (ref "X1") (pin "24") (pinfunction "24_24") (pintype "passive"))
    )
    (net (code "72") (name "Net-(ZüNDSPULE-PP)") (class "Default")
      (node (ref "X1") (pin "16") (pinfunction "16_16") (pintype "passive"))
      (node (ref "ZüNDSPULE") (pin "TP") (pinfunction "PP_TP") (pintype "input"))
    )
    (net (code "73") (name "VCC") (class "Default")
      (node (ref "C4") (pin "1") (pinfunction "1_1") (pintype "passive"))
      (node (ref "IC1") (pin "OUT") (pinfunction "OUT_OUT") (pintype "passive"))
      (node (ref "IC2") (pin "8") (pinfunction "V+_8") (pintype "power_in"))
      (node (ref "IC5") (pin "8") (pinfunction "V+_8") (pintype "power_in"))
      (node (ref "R15") (pin "2") (pinfunction "2_2") (pintype "passive"))
      (node (ref "R6") (pin "2") (pinfunction "2_2") (pintype "passive"))
    )
    (net (code "74") (name "unconnected-(IC3A-Q6-Pad7)") (class "Default")
      (node (ref "IC3") (pin "7") (pinfunction "Q6_7") (pintype "output"))
    )
    (net (code "75") (name "unconnected-(IC3A-Q7-Pad4)") (class "Default")
      (node (ref "IC3") (pin "4") (pinfunction "Q7_4") (pintype "output"))
    )
    (net (code "76") (name "unconnected-(IC3A-Q8-Pad9)") (class "Default")
      (node (ref "IC3") (pin "9") (pinfunction "Q8_9") (pintype "output"))
    )
    (net (code "77") (name "unconnected-(IC3A-Q9-Pad5)") (class "Default")
      (node (ref "IC3") (pin "5") (pinfunction "Q9_5") (pintype "output"))
    )
    (net (code "78") (name "unconnected-(T-C{slash}-Pad4)") (class "Default")
      (node (ref "T") (pin "4") (pinfunction "C/_4") (pintype "passive"))
    )
    (net (code "79") (name "unconnected-(T3-C{slash}-Pad4)") (class "Default")
      (node (ref "T3") (pin "4") (pinfunction "C/_4") (pintype "passive"))
    )
    (net (code "80") (name "unconnected-(T13-C{slash}-Pad4)") (class "Default")
      (node (ref "T13") (pin "4") (pinfunction "C/_4") (pintype "passive"))
    )
    (net (code "81") (name "unconnected-(T14-C{slash}-Pad4)") (class "Default")
      (node (ref "T14") (pin "4") (pinfunction "C/_4") (pintype "passive"))
    )
    (net (code "82") (name "unconnected-(X1-Pad20)") (class "Default")
      (node (ref "X1") (pin "20") (pinfunction "20_20") (pintype "passive"))
    )
  )
)
